# InverterSCH.net
KiCad netlist of a schematic drawn in Altium Designer
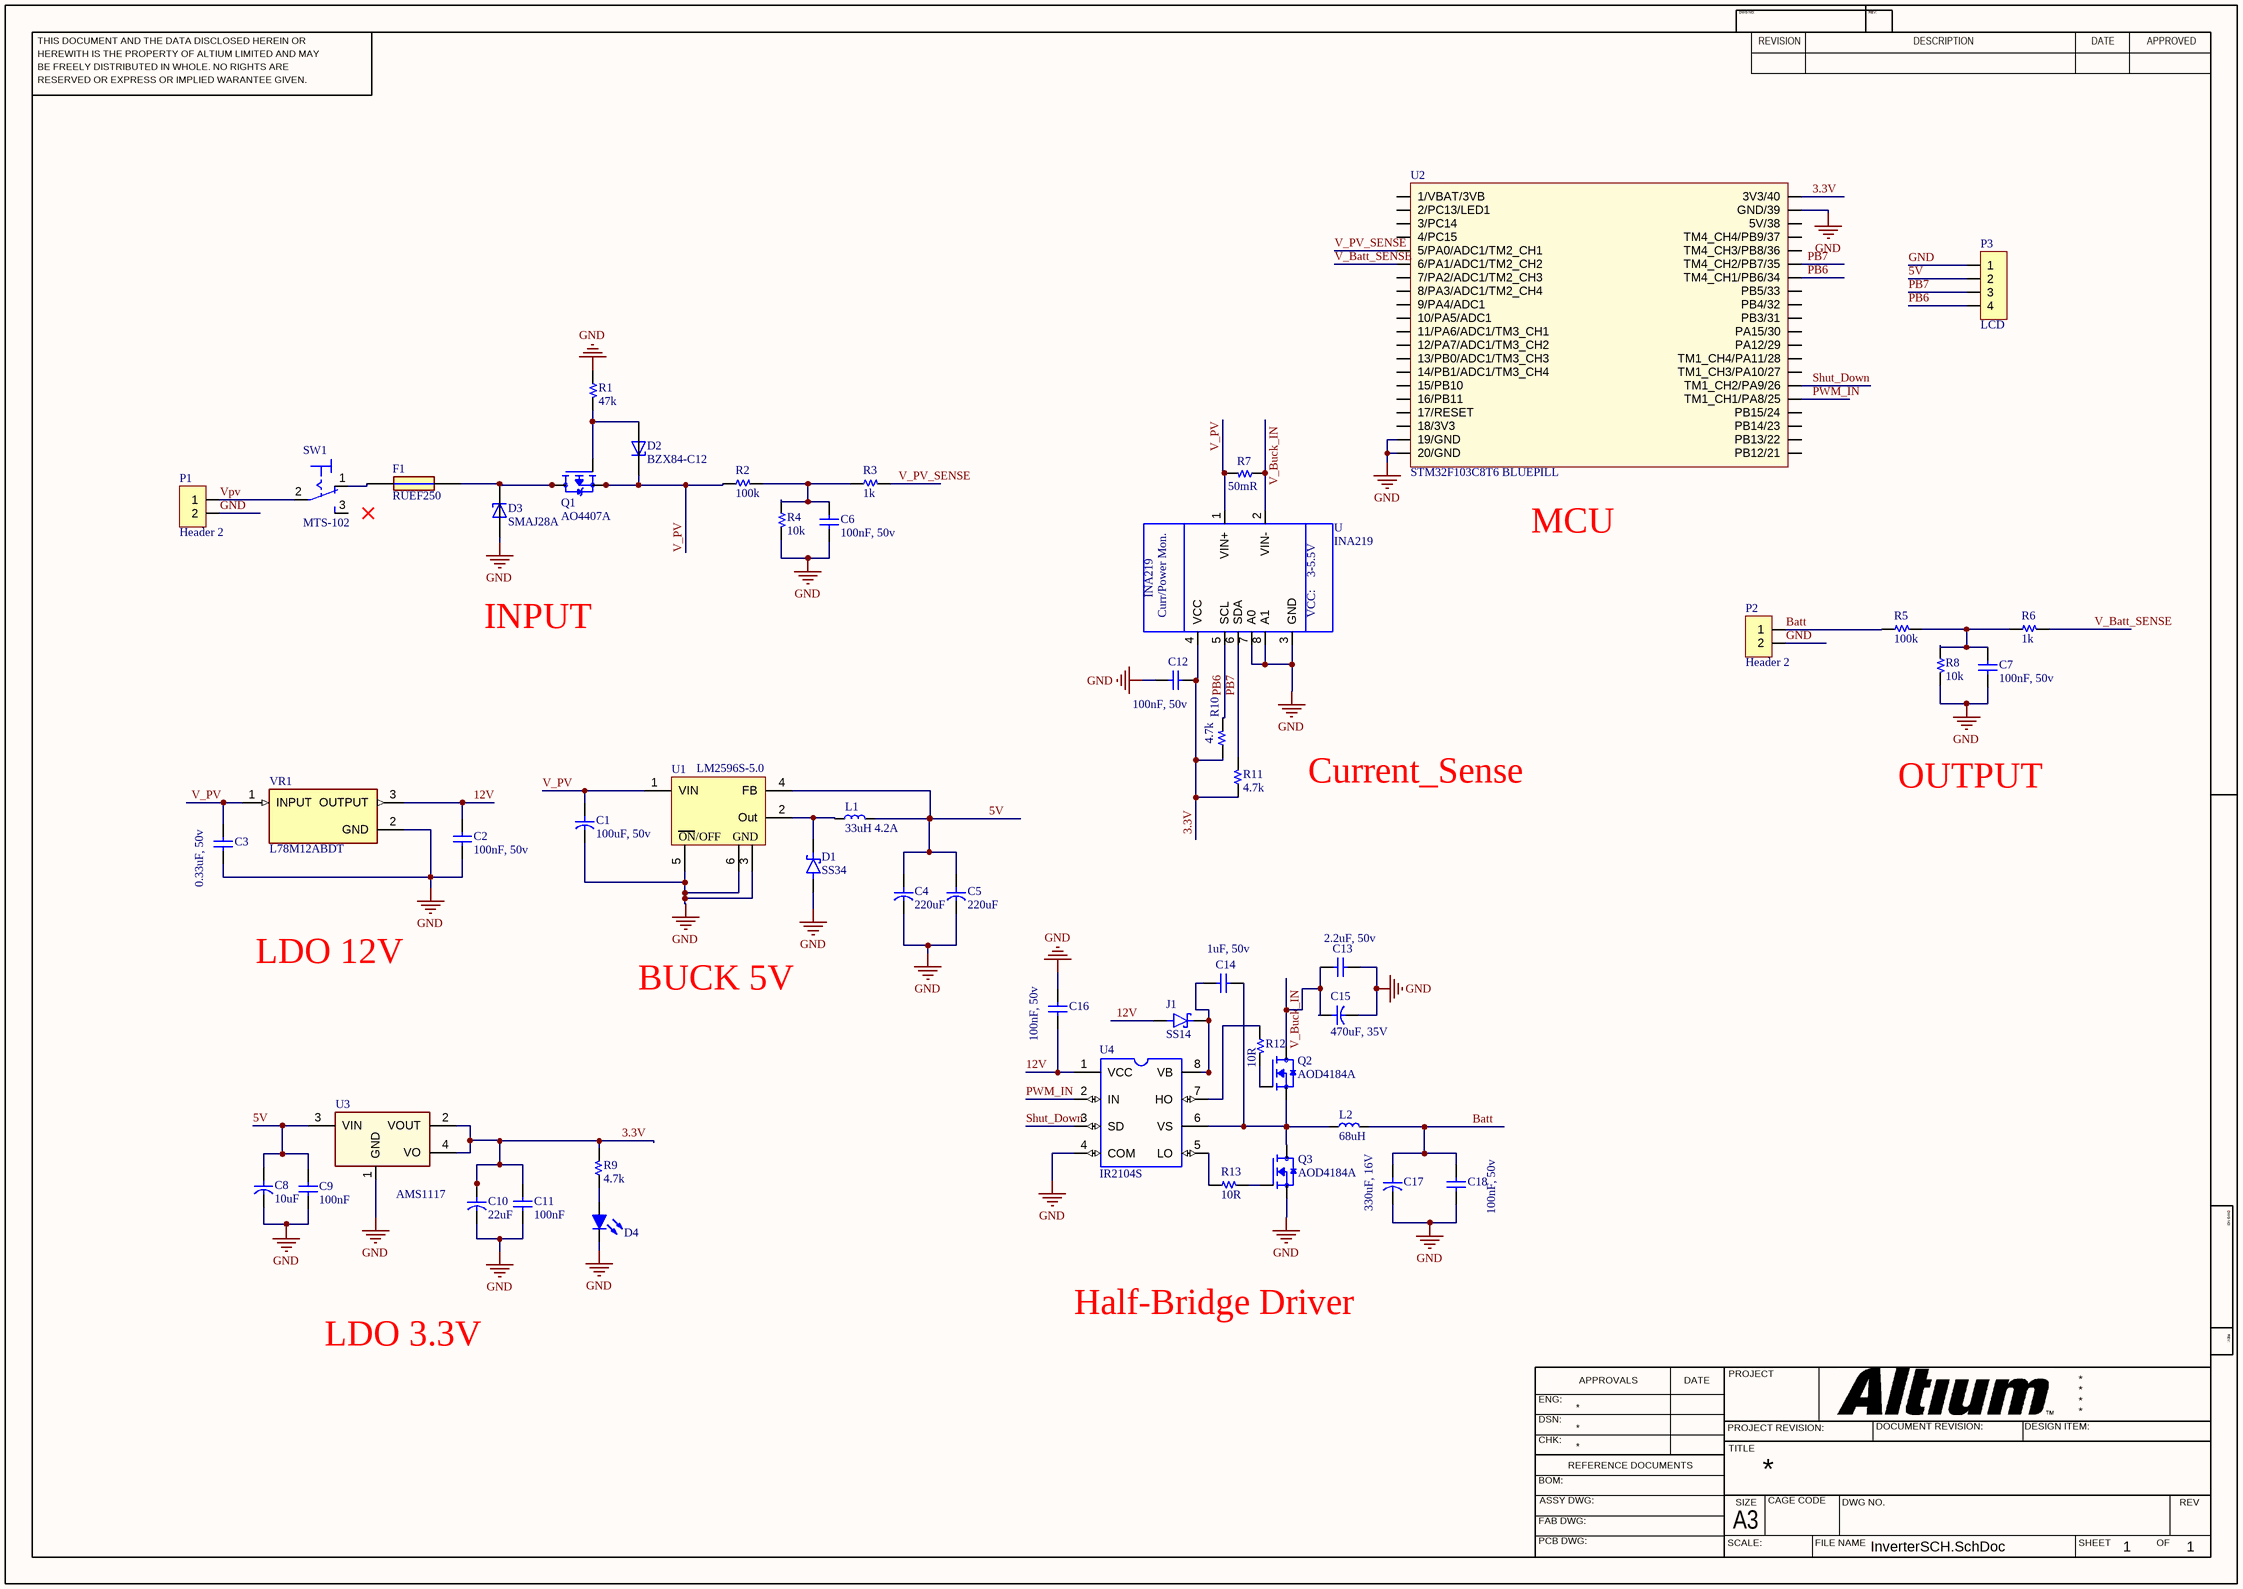
[diagram p0: InverterSCH.SchDoc]

(export (version "E")
  (design (tool "Eeschema 10.0.6"))
  (components
    (comp (ref "C1")
      (value "100uF, 50v")
      (footprint "C SMD TAN 2917 (E)")
      (description "Capacitor pol")
      (libsource (lib "chipfc_altium_libs") (part "Capacitor"))
    )
    (comp (ref "C2")
      (value "100nF, 50v")
      (footprint "C 0603")
      (description "Capacitor non-pol")
      (libsource (lib "chipfc_libs") (part "Capacitor NP"))
    )
    (comp (ref "C3")
      (value "0.33uF, 50v")
      (footprint "C 0805")
      (description "Capacitor non-pol")
      (libsource (lib "chipfc_libs") (part "Capacitor NP"))
    )
    (comp (ref "C4")
      (value "220uF")
      (footprint "C SMD TAN 2312 (C)")
      (description "Capacitor pol")
      (libsource (lib "chipfc_altium_libs") (part "Capacitor"))
    )
    (comp (ref "C5")
      (value "220uF")
      (footprint "C SMD TAN 2312 (C)")
      (description "Capacitor pol")
      (libsource (lib "chipfc_altium_libs") (part "Capacitor"))
    )
    (comp (ref "C6")
      (value "100nF, 50v")
      (footprint "C 0603")
      (description "Capacitor non-pol")
      (libsource (lib "chipfc_libs") (part "Capacitor NP"))
    )
    (comp (ref "C7")
      (value "100nF, 50v")
      (footprint "C 0603")
      (description "Capacitor non-pol")
      (libsource (lib "chipfc_libs") (part "Capacitor NP"))
    )
    (comp (ref "C8")
      (value "10uF")
      (footprint "C SMD ALU (B)")
      (description "Capacitor pol")
      (libsource (lib "chipfc_altium_libs") (part "Capacitor"))
    )
    (comp (ref "C9")
      (value "100nF")
      (footprint "C 0805")
      (description "Capacitor non-pol")
      (libsource (lib "chipfc_altium_libs") (part "Capacitor NP"))
    )
    (comp (ref "C10")
      (value "22uF")
      (footprint "C SMD TAN 2917 (E)")
      (description "Capacitor pol")
      (libsource (lib "chipfc_altium_libs") (part "Capacitor"))
    )
    (comp (ref "C11")
      (value "100nF")
      (footprint "C 0805")
      (description "Capacitor non-pol")
      (libsource (lib "chipfc_altium_libs") (part "Capacitor NP"))
    )
    (comp (ref "C12")
      (value "100nF, 50v")
      (footprint "C 0603")
      (description "Capacitor non-pol")
      (libsource (lib "chipfc_libs") (part "Capacitor NP"))
    )
    (comp (ref "C13")
      (value "2.2uF, 50v")
      (footprint "C 1206")
      (description "Capacitor non-pol")
      (libsource (lib "chipfc_libs") (part "Capacitor NP"))
    )
    (comp (ref "C14")
      (value "1uF, 50v")
      (footprint "C 0603")
      (description "Capacitor non-pol")
      (libsource (lib "chipfc_libs") (part "Capacitor NP"))
    )
    (comp (ref "C15")
      (value "470uF, 35V")
      (footprint "C SMD ALU (D8)")
      (description "Capacitor pol")
      (libsource (lib "chipfc_altium_libs") (part "Capacitor"))
    )
    (comp (ref "C16")
      (value "100nF, 50v")
      (footprint "C 0603")
      (description "Capacitor non-pol")
      (libsource (lib "chipfc_libs") (part "Capacitor NP"))
    )
    (comp (ref "C17")
      (value "330uF, 16V")
      (footprint "C SMD TAN 2917 (E)")
      (description "Capacitor pol")
      (libsource (lib "chipfc_altium_libs") (part "Capacitor"))
    )
    (comp (ref "C18")
      (value "100nF, 50v")
      (footprint "C 0603")
      (description "Capacitor non-pol")
      (libsource (lib "chipfc_libs") (part "Capacitor NP"))
    )
    (comp (ref "D1")
      (value "SS34")
      (footprint "DIOM7959X265N")
      (description "Diode Schottky 40 V 3A Surface Mount SMC (DO-214AB)")
      (fields (field (name "MF") "onsemi"))
      (libsource (lib "SS34") (part "SS34"))
    )
    (comp (ref "D2")
      (value "BZX84-C12")
      (footprint "SOT95P230X110-3N")
      (description "Zener Diode 12 V 250 mW Â±5% Surface Mount TO-236AB")
      (fields (field (name "MF") "Nexperia USA"))
      (libsource (lib "BZX84-C12") (part "BZX84-C12"))
    )
    (comp (ref "D3")
      (value "SMAJ28A")
      (footprint "DIOM4325X250N")
      (description "400W, 32.8V, 5%, Unidirectional, TVS")
      (fields (field (name "MF") "Taiwan Semiconductor"))
      (libsource (lib "SMAJ28A") (part "SMAJ28A"))
    )
    (comp (ref "D4")
      (value "Led")
      (footprint "LED 3MM - green")
      (description "Typical LED")
      (libsource (lib "chipfc_altium_libs") (part "Led"))
    )
    (comp (ref "F1")
      (value "RUEF250")
      (footprint "RUEF250")
      (description "Littelfuse 2.5A Radial Leaded PCB Mount Resettable Fuse, 30V dc")
      (fields (field (name "MOUSER PART NUMBER") "650-RUEF250"))
      (libsource (lib "RUEF250") (part "RUEF250"))
    )
    (comp (ref "J1")
      (value "SS14")
      (footprint "SMA")
      (description "Diode Schottky 40 V 1A Surface Mount DO-214AC (SMA)")
      (fields (field (name "MF") "ON"))
      (libsource (lib "SS14") (part "SS14"))
    )
    (comp (ref "L1")
      (value "33uH 4.2A")
      (footprint "Inductor SMD 12x12x8")
      (description "Inductor")
      (libsource (lib "chipfc_altium_libs") (part "Inductor"))
    )
    (comp (ref "L2")
      (value "68uH")
      (footprint "Inductor SMD 12x12x8")
      (description "Inductor")
      (libsource (lib "chipfc_altium_libs") (part "Inductor"))
    )
    (comp (ref "P1")
      (value "Header 2")
      (footprint "HDR/Terminal/2")
      (description "Header, 2-Pin")
      (libsource (lib "chipfc_altium_libs") (part "Header 2"))
    )
    (comp (ref "P2")
      (value "Header 2")
      (footprint "HDR/Terminal/2")
      (description "Header, 2-Pin")
      (libsource (lib "chipfc_altium_libs") (part "Header 2"))
    )
    (comp (ref "P3")
      (value "LCD")
      (footprint "HDR/Header/4/BOX")
      (description "Header, 4-Pin")
      (libsource (lib "chipfc_altium_libs") (part "Header 4"))
    )
    (comp (ref "Q1")
      (value "AO4407A")
      (footprint "SOIC127P600X175-8N")
      (description "P-Channel 30 V 12A (Ta) 3.1W (Ta) Surface Mount 8-SOIC")
      (fields (field (name "MF") "Alpha &"))
      (libsource (lib "AO4407A") (part "AO4407A"))
    )
    (comp (ref "Q2")
      (value "AOD4184A")
      (footprint "DPAK228P994X240-4N")
      (description "N-Channel 40 V 13A (Ta), 50A (Tc) 2.3W (Ta), 50W (Tc) Surface Mount TO-252 (DPAK)")
      (fields (field (name "MF") "Alpha & Omega Semiconductor Inc."))
      (libsource (lib "AOD4184A") (part "AOD4184A"))
    )
    (comp (ref "Q3")
      (value "AOD4184A")
      (footprint "DPAK228P994X240-4N")
      (description "N-Channel 40 V 13A (Ta), 50A (Tc) 2.3W (Ta), 50W (Tc) Surface Mount TO-252 (DPAK)")
      (fields (field (name "MF") "Alpha & Omega Semiconductor Inc."))
      (libsource (lib "AOD4184A") (part "AOD4184A"))
    )
    (comp (ref "R1")
      (value "47k")
      (footprint "R 0603")
      (description "Resistor")
      (libsource (lib "chipfc_altium_libs") (part "Resistor"))
    )
    (comp (ref "R2")
      (value "100k")
      (footprint "R 0603")
      (description "Resistor")
      (libsource (lib "chipfc_altium_libs") (part "Resistor"))
    )
    (comp (ref "R3")
      (value "1k")
      (footprint "R 0603")
      (description "Resistor")
      (libsource (lib "chipfc_altium_libs") (part "Resistor"))
    )
    (comp (ref "R4")
      (value "10k")
      (footprint "R 0805")
      (description "Resistor")
      (libsource (lib "chipfc_altium_libs") (part "Resistor"))
    )
    (comp (ref "R5")
      (value "100k")
      (footprint "R 0603")
      (description "Resistor")
      (libsource (lib "chipfc_altium_libs") (part "Resistor"))
    )
    (comp (ref "R6")
      (value "1k")
      (footprint "R 0603")
      (description "Resistor")
      (libsource (lib "chipfc_altium_libs") (part "Resistor"))
    )
    (comp (ref "R7")
      (value "50mR")
      (footprint "R 2512")
      (description "Resistor")
      (libsource (lib "chipfc_altium_libs") (part "Resistor"))
    )
    (comp (ref "R8")
      (value "10k")
      (footprint "R 0603")
      (description "Resistor")
      (libsource (lib "chipfc_altium_libs") (part "Resistor"))
    )
    (comp (ref "R9")
      (value "4.7k")
      (footprint "R 1206")
      (description "Resistor")
      (libsource (lib "chipfc_altium_libs") (part "Resistor"))
    )
    (comp (ref "R10")
      (value "4.7k")
      (footprint "R 0603")
      (description "Resistor")
      (libsource (lib "chipfc_altium_libs") (part "Resistor"))
    )
    (comp (ref "R11")
      (value "4.7k")
      (footprint "R 0603")
      (description "Resistor")
      (libsource (lib "chipfc_altium_libs") (part "Resistor"))
    )
    (comp (ref "R12")
      (value "10R")
      (footprint "R 0805")
      (description "Resistor")
      (libsource (lib "chipfc_altium_libs") (part "Resistor"))
    )
    (comp (ref "R13")
      (value "10R")
      (footprint "R 0805")
      (description "Resistor")
      (libsource (lib "chipfc_altium_libs") (part "Resistor"))
    )
    (comp (ref "SW1")
      (value "MTS-102")
      (footprint "MTS-102")
      (description "Rectangular Cable Assemblies .100 Mini Mate Single Row Discrete Wire Cable Assembly, Terminal")
      (fields (field (name "MF") "Motorola") (field (name "MP") "MTS102"))
      (libsource (lib "MTS-102") (part "MTS-102"))
    )
    (comp (ref "U")
      (value "INA219")
      (footprint "SOT23-8")
      (description "Current Monitor Regulator High-Side 10mA SOT-23-8")
      (fields (field (name "MF") "Texas Instruments"))
      (libsource (lib "INA219") (part "INA219"))
    )
    (comp (ref "U1")
      (value "LM2596S-5.0")
      (footprint "TO-263-5")
      (description "Simple Switcher 3A Step-Down Voltage Regulator")
      (libsource (lib "chipfc_altium_libs") (part "LM2596S-5.0"))
    )
    (comp (ref "U2")
      (value "STM32F103C8T6 BLUEPILL")
      (footprint "Female header 20x20 pin")
      (description "Connector 9")
      (libsource (lib "NGHIA") (part "STM32F103C8T6 KIT BLUE PILL"))
    )
    (comp (ref "U3")
      (value "AMS1117")
      (footprint "SOT-223")
      (description "1A LDO Voltage Regulator, ADJ or fixed 1.5/1.8/2.5/2.85/3.3/5V")
      (libsource (lib "chipfc_altium_libs") (part "AMS1117"))
    )
    (comp (ref "U4")
      (value "IR2104S")
      (footprint "IR2104S")
      (description "Half-Bridge Gate Driver IC Non-Inverting 8-SOIC")
      (fields (field (name "MF") "Infineon Technologies"))
      (libsource (lib "IR2104S") (part "IR2104S"))
    )
    (comp (ref "VR1")
      (value "L78M12ABDT")
      (footprint "VREG_L78M12ABDT")
      (description "Linear Voltage Regulator IC Positive Fixed 1 Output 500mA DPAK")
      (fields (field (name "MF") "STMicroelectronics"))
      (libsource (lib "L78M12ABDT") (part "L78M12ABDT"))
    )
  )
  (nets
    (net (code "1") (name "/3.3V") (class "Default")
      (node (ref "C10") (pin "1") (pinfunction "1_1") (pintype "passive"))
      (node (ref "C11") (pin "1") (pinfunction "1_1") (pintype "passive"))
      (node (ref "C12") (pin "1") (pinfunction "1_1") (pintype "passive"))
      (node (ref "R10") (pin "1") (pinfunction "1_1") (pintype "passive"))
      (node (ref "R11") (pin "1") (pinfunction "1_1") (pintype "passive"))
      (node (ref "R9") (pin "2") (pinfunction "2_2") (pintype "passive"))
      (node (ref "U") (pin "4") (pinfunction "VCC_4") (pintype "bidirectional"))
      (node (ref "U2") (pin "40") (pinfunction "3V3/40_40") (pintype "passive"))
      (node (ref "U3") (pin "2") (pinfunction "VOUT_2") (pintype "passive"))
      (node (ref "U3") (pin "4") (pinfunction "VO_4") (pintype "passive"))
    )
    (net (code "2") (name "/5V") (class "Default")
      (node (ref "C4") (pin "1") (pinfunction "1_1") (pintype "passive"))
      (node (ref "C5") (pin "1") (pinfunction "1_1") (pintype "passive"))
      (node (ref "C8") (pin "1") (pinfunction "1_1") (pintype "passive"))
      (node (ref "C9") (pin "1") (pinfunction "1_1") (pintype "passive"))
      (node (ref "L1") (pin "2") (pinfunction "2_2") (pintype "passive"))
      (node (ref "P3") (pin "2") (pinfunction "2_2") (pintype "passive"))
      (node (ref "U1") (pin "4") (pinfunction "FB_4") (pintype "passive"))
      (node (ref "U3") (pin "3") (pinfunction "VIN_3") (pintype "power_in"))
    )
    (net (code "3") (name "/12V") (class "Default")
      (node (ref "C16") (pin "1") (pinfunction "1_1") (pintype "passive"))
      (node (ref "C2") (pin "2") (pinfunction "2_2") (pintype "passive"))
      (node (ref "J1") (pin "P1") (pinfunction "A_P1") (pintype "passive"))
      (node (ref "U4") (pin "1") (pinfunction "VCC_1") (pintype "power_in"))
      (node (ref "VR1") (pin "3") (pinfunction "OUTPUT_3") (pintype "output"))
    )
    (net (code "4") (name "/Batt") (class "Default")
      (node (ref "C17") (pin "1") (pinfunction "1_1") (pintype "passive"))
      (node (ref "C18") (pin "2") (pinfunction "2_2") (pintype "passive"))
      (node (ref "L2") (pin "2") (pinfunction "2_2") (pintype "passive"))
      (node (ref "P2") (pin "1") (pinfunction "1_1") (pintype "passive"))
      (node (ref "R5") (pin "1") (pinfunction "1_1") (pintype "passive"))
    )
    (net (code "5") (name "/PB6") (class "Default")
      (node (ref "P3") (pin "4") (pinfunction "4_4") (pintype "passive"))
      (node (ref "R10") (pin "2") (pinfunction "2_2") (pintype "passive"))
      (node (ref "U") (pin "5") (pinfunction "SCL_5") (pintype "bidirectional"))
      (node (ref "U2") (pin "34") (pinfunction "TM4_CH1/PB6/34_34") (pintype "passive"))
    )
    (net (code "6") (name "/PB7") (class "Default")
      (node (ref "P3") (pin "3") (pinfunction "3_3") (pintype "passive"))
      (node (ref "R11") (pin "2") (pinfunction "2_2") (pintype "passive"))
      (node (ref "U") (pin "6") (pinfunction "SDA_6") (pintype "bidirectional"))
      (node (ref "U2") (pin "35") (pinfunction "TM4_CH2/PB7/35_35") (pintype "passive"))
    )
    (net (code "7") (name "/PWM_IN") (class "Default")
      (node (ref "U2") (pin "25") (pinfunction "TM1_CH1/PA8/25_25") (pintype "passive"))
      (node (ref "U4") (pin "2") (pinfunction "IN_2") (pintype "bidirectional"))
    )
    (net (code "8") (name "/Shut_Down") (class "Default")
      (node (ref "U2") (pin "26") (pinfunction "TM1_CH2/PA9/26_26") (pintype "passive"))
      (node (ref "U4") (pin "3") (pinfunction "SD_3") (pintype "bidirectional"))
    )
    (net (code "9") (name "/V_Batt_SENSE") (class "Default")
      (node (ref "R6") (pin "2") (pinfunction "2_2") (pintype "passive"))
      (node (ref "U2") (pin "6") (pinfunction "6/PA1/ADC1/TM2_CH2_6") (pintype "passive"))
    )
    (net (code "10") (name "/V_Buck_IN") (class "Default")
      (node (ref "C13") (pin "2") (pinfunction "2_2") (pintype "passive"))
      (node (ref "C15") (pin "1") (pinfunction "1_1") (pintype "passive"))
      (node (ref "Q2") (pin "4") (pinfunction "D_4") (pintype "passive"))
      (node (ref "R7") (pin "1") (pinfunction "1_1") (pintype "passive"))
      (node (ref "U") (pin "2") (pinfunction "VIN-_2") (pintype "bidirectional"))
    )
    (net (code "11") (name "/V_PV") (class "Default")
      (node (ref "C1") (pin "1") (pinfunction "1_1") (pintype "passive"))
      (node (ref "C3") (pin "1") (pinfunction "1_1") (pintype "passive"))
      (node (ref "D2") (pin "3") (pinfunction "C_3") (pintype "passive"))
      (node (ref "Q1") (pin "1") (pinfunction "S_1") (pintype "passive"))
      (node (ref "Q1") (pin "2") (pinfunction "S_2") (pintype "passive"))
      (node (ref "Q1") (pin "3") (pinfunction "S_3") (pintype "passive"))
      (node (ref "R2") (pin "1") (pinfunction "1_1") (pintype "passive"))
      (node (ref "R7") (pin "2") (pinfunction "2_2") (pintype "passive"))
      (node (ref "U") (pin "1") (pinfunction "VIN+_1") (pintype "bidirectional"))
      (node (ref "U1") (pin "1") (pinfunction "VIN_1") (pintype "passive"))
      (node (ref "VR1") (pin "1") (pinfunction "INPUT_1") (pintype "input"))
    )
    (net (code "12") (name "/V_PV_SENSE") (class "Default")
      (node (ref "R3") (pin "2") (pinfunction "2_2") (pintype "passive"))
      (node (ref "U2") (pin "5") (pinfunction "5/PA0/ADC1/TM2_CH1_5") (pintype "passive"))
    )
    (net (code "13") (name "/Vpv") (class "Default")
      (node (ref "P1") (pin "1") (pinfunction "1_1") (pintype "passive"))
      (node (ref "SW1") (pin "2") (pinfunction "P_2") (pintype "passive"))
    )
    (net (code "14") (name "GND") (class "Default")
      (node (ref "C1") (pin "2") (pinfunction "2_2") (pintype "passive"))
      (node (ref "C10") (pin "2") (pinfunction "2_2") (pintype "passive"))
      (node (ref "C11") (pin "2") (pinfunction "2_2") (pintype "passive"))
      (node (ref "C12") (pin "2") (pinfunction "2_2") (pintype "passive"))
      (node (ref "C13") (pin "1") (pinfunction "1_1") (pintype "passive"))
      (node (ref "C15") (pin "2") (pinfunction "2_2") (pintype "passive"))
      (node (ref "C16") (pin "2") (pinfunction "2_2") (pintype "passive"))
      (node (ref "C17") (pin "2") (pinfunction "2_2") (pintype "passive"))
      (node (ref "C18") (pin "1") (pinfunction "1_1") (pintype "passive"))
      (node (ref "C2") (pin "1") (pinfunction "1_1") (pintype "passive"))
      (node (ref "C3") (pin "2") (pinfunction "2_2") (pintype "passive"))
      (node (ref "C4") (pin "2") (pinfunction "2_2") (pintype "passive"))
      (node (ref "C5") (pin "2") (pinfunction "2_2") (pintype "passive"))
      (node (ref "C6") (pin "1") (pinfunction "1_1") (pintype "passive"))
      (node (ref "C7") (pin "1") (pinfunction "1_1") (pintype "passive"))
      (node (ref "C8") (pin "2") (pinfunction "2_2") (pintype "passive"))
      (node (ref "C9") (pin "2") (pinfunction "2_2") (pintype "passive"))
      (node (ref "D1") (pin "A") (pinfunction "A_A") (pintype "passive"))
      (node (ref "D3") (pin "A") (pinfunction "A_A") (pintype "passive"))
      (node (ref "D4") (pin "2") (pinfunction "K_2") (pintype "passive"))
      (node (ref "P1") (pin "2") (pinfunction "2_2") (pintype "passive"))
      (node (ref "P2") (pin "2") (pinfunction "2_2") (pintype "passive"))
      (node (ref "P3") (pin "1") (pinfunction "1_1") (pintype "passive"))
      (node (ref "Q3") (pin "3") (pinfunction "S_3") (pintype "passive"))
      (node (ref "R1") (pin "1") (pinfunction "1_1") (pintype "passive"))
      (node (ref "R4") (pin "2") (pinfunction "2_2") (pintype "passive"))
      (node (ref "R8") (pin "2") (pinfunction "2_2") (pintype "passive"))
      (node (ref "U") (pin "3") (pinfunction "GND_3") (pintype "bidirectional"))
      (node (ref "U") (pin "7") (pinfunction "A0_7") (pintype "bidirectional"))
      (node (ref "U") (pin "8") (pinfunction "A1_8") (pintype "bidirectional"))
      (node (ref "U1") (pin "3") (pinfunction "GND_3") (pintype "passive"))
      (node (ref "U1") (pin "5") (pinfunction "~{ON}/OFF_5") (pintype "passive"))
      (node (ref "U1") (pin "6") (pinfunction "PAD_6") (pintype "passive"))
      (node (ref "U2") (pin "19") (pinfunction "19/GND_19") (pintype "passive"))
      (node (ref "U2") (pin "20") (pinfunction "20/GND_20") (pintype "passive"))
      (node (ref "U2") (pin "39") (pinfunction "GND/39_39") (pintype "passive"))
      (node (ref "U3") (pin "1") (pinfunction "GND_1") (pintype "passive"))
      (node (ref "U4") (pin "4") (pinfunction "COM_4") (pintype "bidirectional"))
      (node (ref "VR1") (pin "2") (pinfunction "GND_2") (pintype "power_in"))
    )
    (net (code "15") (name "Net-(C6-Pad2)") (class "Default")
      (node (ref "C6") (pin "2") (pinfunction "2_2") (pintype "passive"))
      (node (ref "R2") (pin "2") (pinfunction "2_2") (pintype "passive"))
      (node (ref "R3") (pin "1") (pinfunction "1_1") (pintype "passive"))
      (node (ref "R4") (pin "1") (pinfunction "1_1") (pintype "passive"))
    )
    (net (code "16") (name "Net-(C7-Pad2)") (class "Default")
      (node (ref "C7") (pin "2") (pinfunction "2_2") (pintype "passive"))
      (node (ref "R5") (pin "2") (pinfunction "2_2") (pintype "passive"))
      (node (ref "R6") (pin "1") (pinfunction "1_1") (pintype "passive"))
      (node (ref "R8") (pin "1") (pinfunction "1_1") (pintype "passive"))
    )
    (net (code "17") (name "Net-(D1-K)") (class "Default")
      (node (ref "D1") (pin "C") (pinfunction "K_C") (pintype "passive"))
      (node (ref "L1") (pin "1") (pinfunction "1_1") (pintype "passive"))
      (node (ref "U1") (pin "2") (pinfunction "Out_2") (pintype "passive"))
    )
    (net (code "18") (name "Net-(D2-A)") (class "Default")
      (node (ref "D2") (pin "1") (pinfunction "A_1") (pintype "passive"))
      (node (ref "Q1") (pin "4") (pinfunction "G_4") (pintype "passive"))
      (node (ref "R1") (pin "2") (pinfunction "2_2") (pintype "passive"))
    )
    (net (code "19") (name "Net-(D3-PadC)") (class "Default")
      (node (ref "D3") (pin "C") (pinfunction "C_C") (pintype "passive"))
      (node (ref "F1") (pin "2") (pinfunction "2_2") (pintype "passive"))
      (node (ref "Q1") (pin "5") (pinfunction "D_5") (pintype "passive"))
      (node (ref "Q1") (pin "6") (pinfunction "D_6") (pintype "passive"))
      (node (ref "Q1") (pin "7") (pinfunction "D_7") (pintype "passive"))
      (node (ref "Q1") (pin "8") (pinfunction "D_8") (pintype "passive"))
    )
    (net (code "20") (name "Net-(D4-A)") (class "Default")
      (node (ref "D4") (pin "1") (pinfunction "A_1") (pintype "passive"))
      (node (ref "R9") (pin "1") (pinfunction "1_1") (pintype "passive"))
    )
    (net (code "21") (name "Net-(J1-C)") (class "Default")
      (node (ref "C14") (pin "2") (pinfunction "2_2") (pintype "passive"))
      (node (ref "J1") (pin "P2") (pinfunction "C_P2") (pintype "passive"))
      (node (ref "U4") (pin "8") (pinfunction "VB_8") (pintype "power_in"))
    )
    (net (code "22") (name "Net-(Q2-G)") (class "Default")
      (node (ref "Q2") (pin "1") (pinfunction "G_1") (pintype "passive"))
      (node (ref "R12") (pin "2") (pinfunction "2_2") (pintype "passive"))
    )
    (net (code "23") (name "Net-(Q2-S)") (class "Default")
      (node (ref "C14") (pin "1") (pinfunction "1_1") (pintype "passive"))
      (node (ref "L2") (pin "1") (pinfunction "1_1") (pintype "passive"))
      (node (ref "Q2") (pin "3") (pinfunction "S_3") (pintype "passive"))
      (node (ref "Q3") (pin "4") (pinfunction "D_4") (pintype "passive"))
      (node (ref "U4") (pin "6") (pinfunction "VS_6") (pintype "power_in"))
    )
    (net (code "24") (name "Net-(Q3-G)") (class "Default")
      (node (ref "Q3") (pin "1") (pinfunction "G_1") (pintype "passive"))
      (node (ref "R13") (pin "2") (pinfunction "2_2") (pintype "passive"))
    )
    (net (code "25") (name "Net-(SW1-O)") (class "Default")
      (node (ref "F1") (pin "1") (pinfunction "1_1") (pintype "passive"))
      (node (ref "SW1") (pin "1") (pinfunction "O_1") (pintype "passive"))
    )
    (net (code "26") (name "Net-(U4-HO)") (class "Default")
      (node (ref "R12") (pin "1") (pinfunction "1_1") (pintype "passive"))
      (node (ref "U4") (pin "7") (pinfunction "HO_7") (pintype "bidirectional"))
    )
    (net (code "27") (name "Net-(U4-LO)") (class "Default")
      (node (ref "R13") (pin "1") (pinfunction "1_1") (pintype "passive"))
      (node (ref "U4") (pin "5") (pinfunction "LO_5") (pintype "bidirectional"))
    )
    (net (code "28") (name "unconnected-(SW1-S-Pad3)") (class "Default")
      (node (ref "SW1") (pin "3") (pinfunction "S_3") (pintype "passive"))
    )
    (net (code "29") (name "unconnected-(U2-1{slash}VBAT{slash}3VB-Pad1)") (class "Default")
      (node (ref "U2") (pin "1") (pinfunction "1/VBAT/3VB_1") (pintype "passive"))
    )
    (net (code "30") (name "unconnected-(U2-2{slash}PC13{slash}LED1-Pad2)") (class "Default")
      (node (ref "U2") (pin "2") (pinfunction "2/PC13/LED1_2") (pintype "passive"))
    )
    (net (code "31") (name "unconnected-(U2-3{slash}PC14-Pad3)") (class "Default")
      (node (ref "U2") (pin "3") (pinfunction "3/PC14_3") (pintype "passive"))
    )
    (net (code "32") (name "unconnected-(U2-4{slash}PC15-Pad4)") (class "Default")
      (node (ref "U2") (pin "4") (pinfunction "4/PC15_4") (pintype "passive"))
    )
    (net (code "33") (name "unconnected-(U2-5V{slash}38-Pad38)") (class "Default")
      (node (ref "U2") (pin "38") (pinfunction "5V/38_38") (pintype "passive"))
    )
    (net (code "34") (name "unconnected-(U2-7{slash}PA2{slash}ADC1{slash}TM2_CH3-Pad7)") (class "Default")
      (node (ref "U2") (pin "7") (pinfunction "7/PA2/ADC1/TM2_CH3_7") (pintype "passive"))
    )
    (net (code "35") (name "unconnected-(U2-8{slash}PA3{slash}ADC1{slash}TM2_CH4-Pad8)") (class "Default")
      (node (ref "U2") (pin "8") (pinfunction "8/PA3/ADC1/TM2_CH4_8") (pintype "passive"))
    )
    (net (code "36") (name "unconnected-(U2-9{slash}PA4{slash}ADC1-Pad9)") (class "Default")
      (node (ref "U2") (pin "9") (pinfunction "9/PA4/ADC1_9") (pintype "passive"))
    )
    (net (code "37") (name "unconnected-(U2-10{slash}PA5{slash}ADC1-Pad10)") (class "Default")
      (node (ref "U2") (pin "10") (pinfunction "10/PA5/ADC1_10") (pintype "passive"))
    )
    (net (code "38") (name "unconnected-(U2-11{slash}PA6{slash}ADC1{slash}TM3_CH1-Pad11)") (class "Default")
      (node (ref "U2") (pin "11") (pinfunction "11/PA6/ADC1/TM3_CH1_11") (pintype "passive"))
    )
    (net (code "39") (name "unconnected-(U2-12{slash}PA7{slash}ADC1{slash}TM3_CH2-Pad12)") (class "Default")
      (node (ref "U2") (pin "12") (pinfunction "12/PA7/ADC1/TM3_CH2_12") (pintype "passive"))
    )
    (net (code "40") (name "unconnected-(U2-13{slash}PB0{slash}ADC1{slash}TM3_CH3-Pad13)") (class "Default")
      (node (ref "U2") (pin "13") (pinfunction "13/PB0/ADC1/TM3_CH3_13") (pintype "passive"))
    )
    (net (code "41") (name "unconnected-(U2-14{slash}PB1{slash}ADC1{slash}TM3_CH4-Pad14)") (class "Default")
      (node (ref "U2") (pin "14") (pinfunction "14/PB1/ADC1/TM3_CH4_14") (pintype "passive"))
    )
    (net (code "42") (name "unconnected-(U2-15{slash}PB10-Pad15)") (class "Default")
      (node (ref "U2") (pin "15") (pinfunction "15/PB10_15") (pintype "passive"))
    )
    (net (code "43") (name "unconnected-(U2-16{slash}PB11-Pad16)") (class "Default")
      (node (ref "U2") (pin "16") (pinfunction "16/PB11_16") (pintype "passive"))
    )
    (net (code "44") (name "unconnected-(U2-17{slash}RESET-Pad17)") (class "Default")
      (node (ref "U2") (pin "17") (pinfunction "17/RESET_17") (pintype "passive"))
    )
    (net (code "45") (name "unconnected-(U2-18{slash}3V3-Pad18)") (class "Default")
      (node (ref "U2") (pin "18") (pinfunction "18/3V3_18") (pintype "passive"))
    )
    (net (code "46") (name "unconnected-(U2-PA12{slash}29-Pad29)") (class "Default")
      (node (ref "U2") (pin "29") (pinfunction "PA12/29_29") (pintype "passive"))
    )
    (net (code "47") (name "unconnected-(U2-PA15{slash}30-Pad30)") (class "Default")
      (node (ref "U2") (pin "30") (pinfunction "PA15/30_30") (pintype "passive"))
    )
    (net (code "48") (name "unconnected-(U2-PB3{slash}31-Pad31)") (class "Default")
      (node (ref "U2") (pin "31") (pinfunction "PB3/31_31") (pintype "passive"))
    )
    (net (code "49") (name "unconnected-(U2-PB4{slash}32-Pad32)") (class "Default")
      (node (ref "U2") (pin "32") (pinfunction "PB4/32_32") (pintype "passive"))
    )
    (net (code "50") (name "unconnected-(U2-PB5{slash}33-Pad33)") (class "Default")
      (node (ref "U2") (pin "33") (pinfunction "PB5/33_33") (pintype "passive"))
    )
    (net (code "51") (name "unconnected-(U2-PB12{slash}21-Pad21)") (class "Default")
      (node (ref "U2") (pin "21") (pinfunction "PB12/21_21") (pintype "passive"))
    )
    (net (code "52") (name "unconnected-(U2-PB13{slash}22-Pad22)") (class "Default")
      (node (ref "U2") (pin "22") (pinfunction "PB13/22_22") (pintype "passive"))
    )
    (net (code "53") (name "unconnected-(U2-PB14{slash}23-Pad23)") (class "Default")
      (node (ref "U2") (pin "23") (pinfunction "PB14/23_23") (pintype "passive"))
    )
    (net (code "54") (name "unconnected-(U2-PB15{slash}24-Pad24)") (class "Default")
      (node (ref "U2") (pin "24") (pinfunction "PB15/24_24") (pintype "passive"))
    )
    (net (code "55") (name "unconnected-(U2-TM1_CH3{slash}PA10{slash}27-Pad27)") (class "Default")
      (node (ref "U2") (pin "27") (pinfunction "TM1_CH3/PA10/27_27") (pintype "passive"))
    )
    (net (code "56") (name "unconnected-(U2-TM1_CH4{slash}PA11{slash}28-Pad28)") (class "Default")
      (node (ref "U2") (pin "28") (pinfunction "TM1_CH4/PA11/28_28") (pintype "passive"))
    )
    (net (code "57") (name "unconnected-(U2-TM4_CH3{slash}PB8{slash}36-Pad36)") (class "Default")
      (node (ref "U2") (pin "36") (pinfunction "TM4_CH3/PB8/36_36") (pintype "passive"))
    )
    (net (code "58") (name "unconnected-(U2-TM4_CH4{slash}PB9{slash}37-Pad37)") (class "Default")
      (node (ref "U2") (pin "37") (pinfunction "TM4_CH4/PB9/37_37") (pintype "passive"))
    )
  )
)
